# Sheet2.net
KiCad netlist of a schematic drawn in Altium Designer
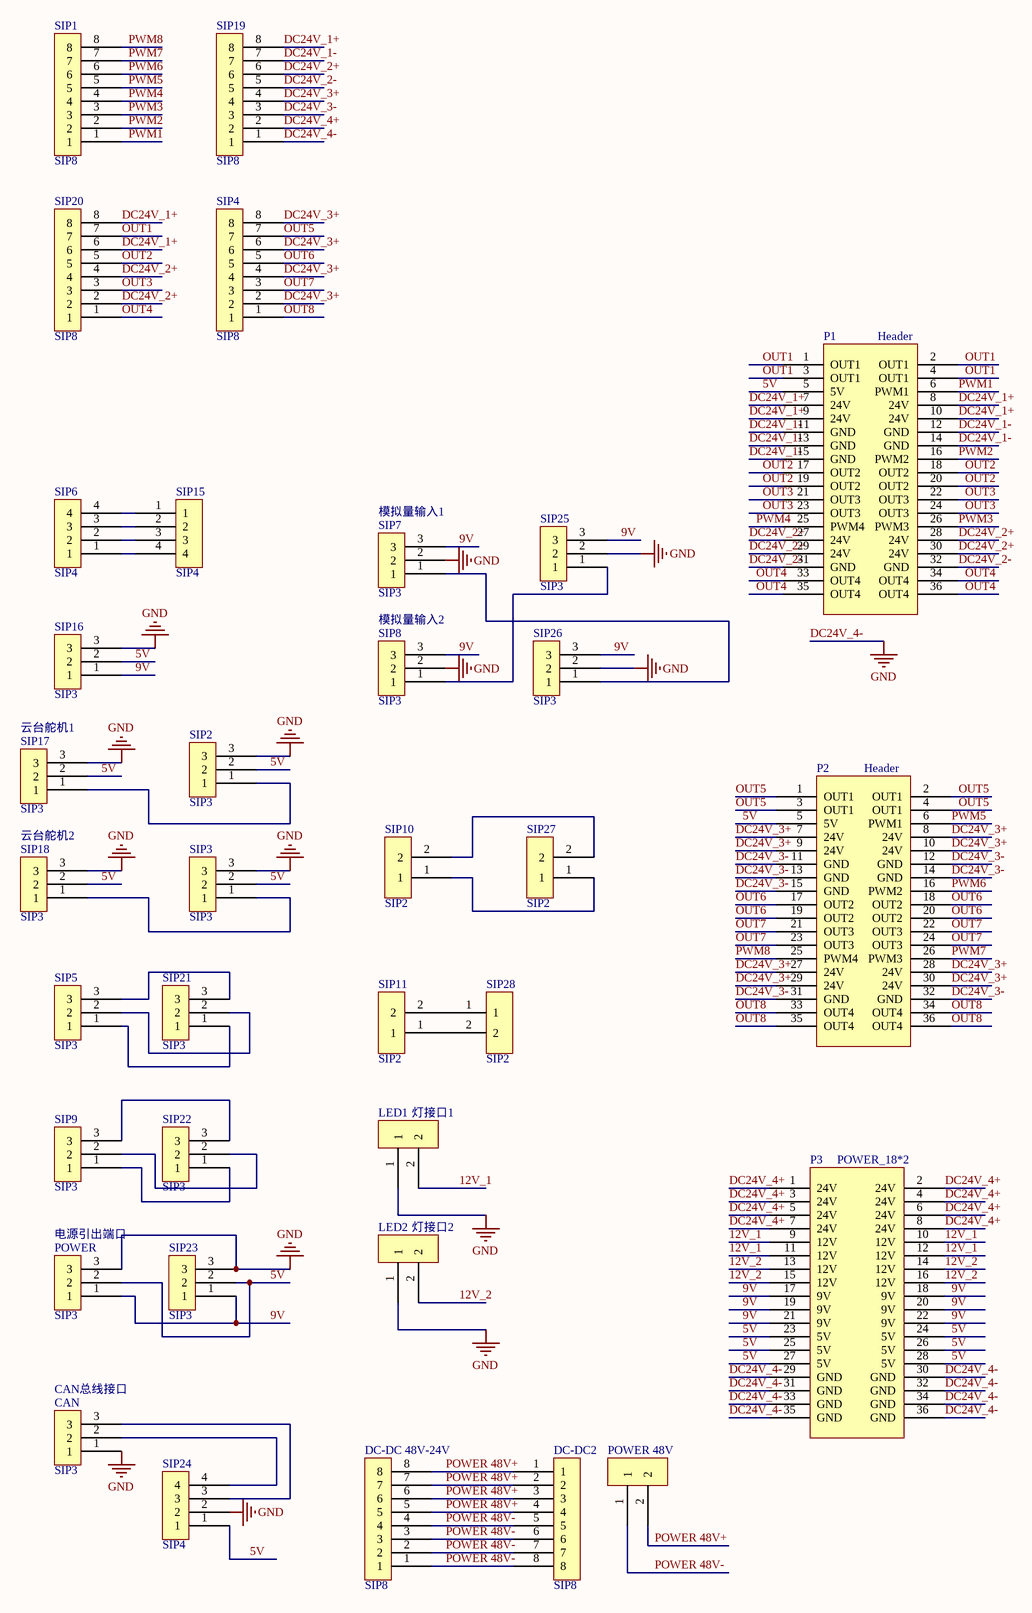
[diagram p0: Sheet2.SchDoc]

(export (version "E")
  (design (tool "Eeschema 10.0.6"))
  (components
    (comp (ref "CAN") (value "SIP3") (footprint "SIP3") (libsource (lib "qudong") (part "SIP3")))
    (comp (ref "DC-DC 48V-24V")
      (value "SIP8")
      (footprint "DIP8-3MM")
      (libsource (lib "qudong") (part "SIP8"))
    )
    (comp (ref "DC-DC2") (value "SIP8") (footprint "DIP8-3MM") (libsource (lib "") (part "SIP8_1")))
    (comp (ref "LED1") (value "SIP2") (footprint "SIP2-3MM") (libsource (lib "") (part "SIP2_2")))
    (comp (ref "LED2") (value "SIP2") (footprint "SIP2-3MM") (libsource (lib "") (part "SIP2_2")))
    (comp (ref "P1") (value "Header") (footprint "DIP36-3.96MM") (libsource (lib "qudong") (part "Header")))
    (comp (ref "P2") (value "Header") (footprint "DIP36-3.96MM") (libsource (lib "qudong") (part "Header")))
    (comp (ref "P3")
      (value "POWER_18*2")
      (footprint "DIP36-3.96MM")
      (libsource (lib "qudong") (part "POWER_18*2"))
    )
    (comp (ref "POWER") (value "SIP3") (footprint "SIP3") (libsource (lib "qudong") (part "SIP3")))
    (comp (ref "POWER 48V") (value "SIP2") (footprint "SIP2-3MM") (libsource (lib "") (part "SIP2_2")))
    (comp (ref "SIP1") (value "SIP8") (footprint "SIP8") (libsource (lib "qudong") (part "SIP8")))
    (comp (ref "SIP2") (value "SIP3") (footprint "SIP3") (libsource (lib "qudong") (part "SIP3")))
    (comp (ref "SIP3") (value "SIP3") (footprint "SIP3") (libsource (lib "qudong") (part "SIP3")))
    (comp (ref "SIP4") (value "SIP8") (footprint "DIP8-3MM") (libsource (lib "qudong") (part "SIP8")))
    (comp (ref "SIP5") (value "SIP3") (footprint "SIP3") (libsource (lib "qudong") (part "SIP3")))
    (comp (ref "SIP6") (value "SIP4") (footprint "SIP4") (libsource (lib "qudong") (part "SIP4")))
    (comp (ref "SIP7") (value "SIP3") (footprint "SIP3") (libsource (lib "qudong") (part "SIP3")))
    (comp (ref "SIP8") (value "SIP3") (footprint "SIP3") (libsource (lib "qudong") (part "SIP3")))
    (comp (ref "SIP9") (value "SIP3") (footprint "SIP3") (libsource (lib "qudong") (part "SIP3")))
    (comp (ref "SIP10") (value "SIP2") (footprint "SIP2") (libsource (lib "qudong") (part "SIP2")))
    (comp (ref "SIP11") (value "SIP2") (footprint "SIP2") (libsource (lib "qudong") (part "SIP2")))
    (comp (ref "SIP15") (value "SIP4") (footprint "SIP4") (libsource (lib "") (part "SIP4_1")))
    (comp (ref "SIP16") (value "SIP3") (footprint "SIP3") (libsource (lib "qudong") (part "SIP3")))
    (comp (ref "SIP17") (value "SIP3") (footprint "SIP3") (libsource (lib "qudong") (part "SIP3")))
    (comp (ref "SIP18") (value "SIP3") (footprint "SIP3") (libsource (lib "qudong") (part "SIP3")))
    (comp (ref "SIP19") (value "SIP8") (footprint "DIP8-3MM") (libsource (lib "qudong") (part "SIP8")))
    (comp (ref "SIP20") (value "SIP8") (footprint "DIP8-3MM") (libsource (lib "qudong") (part "SIP8")))
    (comp (ref "SIP21") (value "SIP3") (footprint "SIP3") (libsource (lib "qudong") (part "SIP3")))
    (comp (ref "SIP22") (value "SIP3") (footprint "SIP3") (libsource (lib "qudong") (part "SIP3")))
    (comp (ref "SIP23") (value "SIP3") (footprint "SIP3") (libsource (lib "qudong") (part "SIP3")))
    (comp (ref "SIP24") (value "SIP4") (footprint "SIP4") (libsource (lib "qudong") (part "SIP4")))
    (comp (ref "SIP25") (value "SIP3") (footprint "SIP3") (libsource (lib "qudong") (part "SIP3")))
    (comp (ref "SIP26") (value "SIP3") (footprint "SIP3") (libsource (lib "qudong") (part "SIP3")))
    (comp (ref "SIP27") (value "SIP2") (footprint "SIP2") (libsource (lib "qudong") (part "SIP2")))
    (comp (ref "SIP28") (value "SIP2") (footprint "SIP2") (libsource (lib "") (part "SIP2_1")))
  )
  (nets
    (net (code "1") (name "/5V") (class "Default")
      (node (ref "P1") (pin "5") (pinfunction "5V_5") (pintype "passive"))
      (node (ref "P2") (pin "5") (pinfunction "5V_5") (pintype "passive"))
      (node (ref "P3") (pin "23") (pinfunction "5V_23") (pintype "passive"))
      (node (ref "P3") (pin "24") (pinfunction "5V_24") (pintype "passive"))
      (node (ref "P3") (pin "25") (pinfunction "5V_25") (pintype "passive"))
      (node (ref "P3") (pin "26") (pinfunction "5V_26") (pintype "passive"))
      (node (ref "P3") (pin "27") (pinfunction "5V_27") (pintype "passive"))
      (node (ref "P3") (pin "28") (pinfunction "5V_28") (pintype "passive"))
      (node (ref "POWER") (pin "2") (pinfunction "2_2") (pintype "passive"))
      (node (ref "SIP16") (pin "2") (pinfunction "2_2") (pintype "passive"))
      (node (ref "SIP17") (pin "2") (pinfunction "2_2") (pintype "passive"))
      (node (ref "SIP18") (pin "2") (pinfunction "2_2") (pintype "passive"))
      (node (ref "SIP2") (pin "2") (pinfunction "2_2") (pintype "passive"))
      (node (ref "SIP23") (pin "2") (pinfunction "2_2") (pintype "passive"))
      (node (ref "SIP24") (pin "1") (pinfunction "1_1") (pintype "passive"))
      (node (ref "SIP3") (pin "2") (pinfunction "2_2") (pintype "passive"))
    )
    (net (code "2") (name "/9V") (class "Default")
      (node (ref "P3") (pin "17") (pinfunction "9V_17") (pintype "passive"))
      (node (ref "P3") (pin "18") (pinfunction "9V_18") (pintype "passive"))
      (node (ref "P3") (pin "19") (pinfunction "9V_19") (pintype "passive"))
      (node (ref "P3") (pin "20") (pinfunction "9V_20") (pintype "passive"))
      (node (ref "P3") (pin "21") (pinfunction "9V_21") (pintype "passive"))
      (node (ref "P3") (pin "22") (pinfunction "9V_22") (pintype "passive"))
      (node (ref "POWER") (pin "1") (pinfunction "1_1") (pintype "passive"))
      (node (ref "SIP16") (pin "1") (pinfunction "1_1") (pintype "passive"))
      (node (ref "SIP23") (pin "1") (pinfunction "1_1") (pintype "passive"))
      (node (ref "SIP25") (pin "3") (pinfunction "3_3") (pintype "passive"))
      (node (ref "SIP26") (pin "3") (pinfunction "3_3") (pintype "passive"))
      (node (ref "SIP7") (pin "3") (pinfunction "3_3") (pintype "passive"))
      (node (ref "SIP8") (pin "3") (pinfunction "3_3") (pintype "passive"))
    )
    (net (code "3") (name "/12V_1") (class "Default")
      (node (ref "LED1") (pin "2") (pinfunction "2_2") (pintype "passive"))
      (node (ref "P3") (pin "10") (pinfunction "12V_10") (pintype "passive"))
      (node (ref "P3") (pin "11") (pinfunction "12V_11") (pintype "passive"))
      (node (ref "P3") (pin "12") (pinfunction "12V_12") (pintype "passive"))
      (node (ref "P3") (pin "9") (pinfunction "12V_9") (pintype "passive"))
    )
    (net (code "4") (name "/12V_2") (class "Default")
      (node (ref "LED2") (pin "2") (pinfunction "2_2") (pintype "passive"))
      (node (ref "P3") (pin "13") (pinfunction "12V_13") (pintype "passive"))
      (node (ref "P3") (pin "14") (pinfunction "12V_14") (pintype "passive"))
      (node (ref "P3") (pin "15") (pinfunction "12V_15") (pintype "passive"))
      (node (ref "P3") (pin "16") (pinfunction "12V_16") (pintype "passive"))
    )
    (net (code "5") (name "/DC24V_1+") (class "Default")
      (node (ref "P1") (pin "10") (pinfunction "24V_10") (pintype "passive"))
      (node (ref "P1") (pin "7") (pinfunction "24V_7") (pintype "passive"))
      (node (ref "P1") (pin "8") (pinfunction "24V_8") (pintype "passive"))
      (node (ref "P1") (pin "9") (pinfunction "24V_9") (pintype "passive"))
      (node (ref "SIP19") (pin "8") (pinfunction "8_8") (pintype "passive"))
      (node (ref "SIP20") (pin "6") (pinfunction "6_6") (pintype "passive"))
      (node (ref "SIP20") (pin "8") (pinfunction "8_8") (pintype "passive"))
    )
    (net (code "6") (name "/DC24V_1-") (class "Default")
      (node (ref "P1") (pin "11") (pinfunction "GND_11") (pintype "passive"))
      (node (ref "P1") (pin "12") (pinfunction "GND_12") (pintype "passive"))
      (node (ref "P1") (pin "13") (pinfunction "GND_13") (pintype "passive"))
      (node (ref "P1") (pin "14") (pinfunction "GND_14") (pintype "passive"))
      (node (ref "P1") (pin "15") (pinfunction "GND_15") (pintype "passive"))
      (node (ref "SIP19") (pin "7") (pinfunction "7_7") (pintype "passive"))
    )
    (net (code "7") (name "/DC24V_2+") (class "Default")
      (node (ref "P1") (pin "27") (pinfunction "24V_27") (pintype "passive"))
      (node (ref "P1") (pin "28") (pinfunction "24V_28") (pintype "passive"))
      (node (ref "P1") (pin "29") (pinfunction "24V_29") (pintype "passive"))
      (node (ref "P1") (pin "30") (pinfunction "24V_30") (pintype "passive"))
      (node (ref "SIP19") (pin "6") (pinfunction "6_6") (pintype "passive"))
      (node (ref "SIP20") (pin "2") (pinfunction "2_2") (pintype "passive"))
      (node (ref "SIP20") (pin "4") (pinfunction "4_4") (pintype "passive"))
    )
    (net (code "8") (name "/DC24V_2-") (class "Default")
      (node (ref "P1") (pin "31") (pinfunction "GND_31") (pintype "passive"))
      (node (ref "P1") (pin "32") (pinfunction "GND_32") (pintype "passive"))
      (node (ref "SIP19") (pin "5") (pinfunction "5_5") (pintype "passive"))
    )
    (net (code "9") (name "/DC24V_3+") (class "Default")
      (node (ref "P2") (pin "10") (pinfunction "24V_10") (pintype "passive"))
      (node (ref "P2") (pin "27") (pinfunction "24V_27") (pintype "passive"))
      (node (ref "P2") (pin "28") (pinfunction "24V_28") (pintype "passive"))
      (node (ref "P2") (pin "29") (pinfunction "24V_29") (pintype "passive"))
      (node (ref "P2") (pin "30") (pinfunction "24V_30") (pintype "passive"))
      (node (ref "P2") (pin "7") (pinfunction "24V_7") (pintype "passive"))
      (node (ref "P2") (pin "8") (pinfunction "24V_8") (pintype "passive"))
      (node (ref "P2") (pin "9") (pinfunction "24V_9") (pintype "passive"))
      (node (ref "SIP19") (pin "4") (pinfunction "4_4") (pintype "passive"))
      (node (ref "SIP4") (pin "2") (pinfunction "2_2") (pintype "passive"))
      (node (ref "SIP4") (pin "4") (pinfunction "4_4") (pintype "passive"))
      (node (ref "SIP4") (pin "6") (pinfunction "6_6") (pintype "passive"))
      (node (ref "SIP4") (pin "8") (pinfunction "8_8") (pintype "passive"))
    )
    (net (code "10") (name "/DC24V_3-") (class "Default")
      (node (ref "P2") (pin "11") (pinfunction "GND_11") (pintype "passive"))
      (node (ref "P2") (pin "12") (pinfunction "GND_12") (pintype "passive"))
      (node (ref "P2") (pin "13") (pinfunction "GND_13") (pintype "passive"))
      (node (ref "P2") (pin "14") (pinfunction "GND_14") (pintype "passive"))
      (node (ref "P2") (pin "15") (pinfunction "GND_15") (pintype "passive"))
      (node (ref "P2") (pin "31") (pinfunction "GND_31") (pintype "passive"))
      (node (ref "P2") (pin "32") (pinfunction "GND_32") (pintype "passive"))
      (node (ref "SIP19") (pin "3") (pinfunction "3_3") (pintype "passive"))
    )
    (net (code "11") (name "/DC24V_4+") (class "Default")
      (node (ref "P3") (pin "1") (pinfunction "24V_1") (pintype "passive"))
      (node (ref "P3") (pin "2") (pinfunction "24V_2") (pintype "passive"))
      (node (ref "P3") (pin "3") (pinfunction "24V_3") (pintype "passive"))
      (node (ref "P3") (pin "4") (pinfunction "24V_4") (pintype "passive"))
      (node (ref "P3") (pin "5") (pinfunction "24V_5") (pintype "passive"))
      (node (ref "P3") (pin "6") (pinfunction "24V_6") (pintype "passive"))
      (node (ref "P3") (pin "7") (pinfunction "24V_7") (pintype "passive"))
      (node (ref "P3") (pin "8") (pinfunction "24V_8") (pintype "passive"))
      (node (ref "SIP19") (pin "2") (pinfunction "2_2") (pintype "passive"))
    )
    (net (code "12") (name "/OUT1") (class "Default")
      (node (ref "P1") (pin "1") (pinfunction "OUT1_1") (pintype "passive"))
      (node (ref "P1") (pin "2") (pinfunction "OUT1_2") (pintype "passive"))
      (node (ref "P1") (pin "3") (pinfunction "OUT1_3") (pintype "passive"))
      (node (ref "P1") (pin "4") (pinfunction "OUT1_4") (pintype "passive"))
      (node (ref "SIP20") (pin "7") (pinfunction "7_7") (pintype "passive"))
    )
    (net (code "13") (name "/OUT2") (class "Default")
      (node (ref "P1") (pin "17") (pinfunction "OUT2_17") (pintype "passive"))
      (node (ref "P1") (pin "18") (pinfunction "OUT2_18") (pintype "passive"))
      (node (ref "P1") (pin "19") (pinfunction "OUT2_19") (pintype "passive"))
      (node (ref "P1") (pin "20") (pinfunction "OUT2_20") (pintype "passive"))
      (node (ref "SIP20") (pin "5") (pinfunction "5_5") (pintype "passive"))
    )
    (net (code "14") (name "/OUT3") (class "Default")
      (node (ref "P1") (pin "21") (pinfunction "OUT3_21") (pintype "passive"))
      (node (ref "P1") (pin "22") (pinfunction "OUT3_22") (pintype "passive"))
      (node (ref "P1") (pin "23") (pinfunction "OUT3_23") (pintype "passive"))
      (node (ref "P1") (pin "24") (pinfunction "OUT3_24") (pintype "passive"))
      (node (ref "SIP20") (pin "3") (pinfunction "3_3") (pintype "passive"))
    )
    (net (code "15") (name "/OUT4") (class "Default")
      (node (ref "P1") (pin "33") (pinfunction "OUT4_33") (pintype "passive"))
      (node (ref "P1") (pin "34") (pinfunction "OUT4_34") (pintype "passive"))
      (node (ref "P1") (pin "35") (pinfunction "OUT4_35") (pintype "passive"))
      (node (ref "P1") (pin "36") (pinfunction "OUT4_36") (pintype "passive"))
      (node (ref "SIP20") (pin "1") (pinfunction "1_1") (pintype "passive"))
    )
    (net (code "16") (name "/OUT5") (class "Default")
      (node (ref "P2") (pin "1") (pinfunction "OUT1_1") (pintype "passive"))
      (node (ref "P2") (pin "2") (pinfunction "OUT1_2") (pintype "passive"))
      (node (ref "P2") (pin "3") (pinfunction "OUT1_3") (pintype "passive"))
      (node (ref "P2") (pin "4") (pinfunction "OUT1_4") (pintype "passive"))
      (node (ref "SIP4") (pin "7") (pinfunction "7_7") (pintype "passive"))
    )
    (net (code "17") (name "/OUT6") (class "Default")
      (node (ref "P2") (pin "17") (pinfunction "OUT2_17") (pintype "passive"))
      (node (ref "P2") (pin "18") (pinfunction "OUT2_18") (pintype "passive"))
      (node (ref "P2") (pin "19") (pinfunction "OUT2_19") (pintype "passive"))
      (node (ref "P2") (pin "20") (pinfunction "OUT2_20") (pintype "passive"))
      (node (ref "SIP4") (pin "5") (pinfunction "5_5") (pintype "passive"))
    )
    (net (code "18") (name "/OUT7") (class "Default")
      (node (ref "P2") (pin "21") (pinfunction "OUT3_21") (pintype "passive"))
      (node (ref "P2") (pin "22") (pinfunction "OUT3_22") (pintype "passive"))
      (node (ref "P2") (pin "23") (pinfunction "OUT3_23") (pintype "passive"))
      (node (ref "P2") (pin "24") (pinfunction "OUT3_24") (pintype "passive"))
      (node (ref "SIP4") (pin "3") (pinfunction "3_3") (pintype "passive"))
    )
    (net (code "19") (name "/OUT8") (class "Default")
      (node (ref "P2") (pin "33") (pinfunction "OUT4_33") (pintype "passive"))
      (node (ref "P2") (pin "34") (pinfunction "OUT4_34") (pintype "passive"))
      (node (ref "P2") (pin "35") (pinfunction "OUT4_35") (pintype "passive"))
      (node (ref "P2") (pin "36") (pinfunction "OUT4_36") (pintype "passive"))
      (node (ref "SIP4") (pin "1") (pinfunction "1_1") (pintype "passive"))
    )
    (net (code "20") (name "/POWER 48V+") (class "Default")
      (node (ref "DC-DC 48V-24V") (pin "5") (pinfunction "5_5") (pintype "passive"))
      (node (ref "DC-DC 48V-24V") (pin "6") (pinfunction "6_6") (pintype "passive"))
      (node (ref "DC-DC 48V-24V") (pin "7") (pinfunction "7_7") (pintype "passive"))
      (node (ref "DC-DC 48V-24V") (pin "8") (pinfunction "8_8") (pintype "passive"))
      (node (ref "DC-DC2") (pin "1") (pinfunction "1_1") (pintype "passive"))
      (node (ref "DC-DC2") (pin "2") (pinfunction "2_2") (pintype "passive"))
      (node (ref "DC-DC2") (pin "3") (pinfunction "3_3") (pintype "passive"))
      (node (ref "DC-DC2") (pin "4") (pinfunction "4_4") (pintype "passive"))
      (node (ref "POWER 48V") (pin "2") (pinfunction "2_2") (pintype "passive"))
    )
    (net (code "21") (name "/POWER 48V-") (class "Default")
      (node (ref "DC-DC 48V-24V") (pin "1") (pinfunction "1_1") (pintype "passive"))
      (node (ref "DC-DC 48V-24V") (pin "2") (pinfunction "2_2") (pintype "passive"))
      (node (ref "DC-DC 48V-24V") (pin "3") (pinfunction "3_3") (pintype "passive"))
      (node (ref "DC-DC 48V-24V") (pin "4") (pinfunction "4_4") (pintype "passive"))
      (node (ref "DC-DC2") (pin "5") (pinfunction "5_5") (pintype "passive"))
      (node (ref "DC-DC2") (pin "6") (pinfunction "6_6") (pintype "passive"))
      (node (ref "DC-DC2") (pin "7") (pinfunction "7_7") (pintype "passive"))
      (node (ref "DC-DC2") (pin "8") (pinfunction "8_8") (pintype "passive"))
      (node (ref "POWER 48V") (pin "1") (pinfunction "1_1") (pintype "passive"))
    )
    (net (code "22") (name "/PWM1") (class "Default")
      (node (ref "P1") (pin "6") (pinfunction "PWM1_6") (pintype "passive"))
      (node (ref "SIP1") (pin "1") (pinfunction "1_1") (pintype "passive"))
    )
    (net (code "23") (name "/PWM2") (class "Default")
      (node (ref "P1") (pin "16") (pinfunction "PWM2_16") (pintype "passive"))
      (node (ref "SIP1") (pin "2") (pinfunction "2_2") (pintype "passive"))
    )
    (net (code "24") (name "/PWM3") (class "Default")
      (node (ref "P1") (pin "26") (pinfunction "PWM3_26") (pintype "passive"))
      (node (ref "SIP1") (pin "3") (pinfunction "3_3") (pintype "passive"))
    )
    (net (code "25") (name "/PWM4") (class "Default")
      (node (ref "P1") (pin "25") (pinfunction "PWM4_25") (pintype "passive"))
      (node (ref "SIP1") (pin "4") (pinfunction "4_4") (pintype "passive"))
    )
    (net (code "26") (name "/PWM5") (class "Default")
      (node (ref "P2") (pin "6") (pinfunction "PWM1_6") (pintype "passive"))
      (node (ref "SIP1") (pin "5") (pinfunction "5_5") (pintype "passive"))
    )
    (net (code "27") (name "/PWM6") (class "Default")
      (node (ref "P2") (pin "16") (pinfunction "PWM2_16") (pintype "passive"))
      (node (ref "SIP1") (pin "6") (pinfunction "6_6") (pintype "passive"))
    )
    (net (code "28") (name "/PWM7") (class "Default")
      (node (ref "P2") (pin "26") (pinfunction "PWM3_26") (pintype "passive"))
      (node (ref "SIP1") (pin "7") (pinfunction "7_7") (pintype "passive"))
    )
    (net (code "29") (name "/PWM8") (class "Default")
      (node (ref "P2") (pin "25") (pinfunction "PWM4_25") (pintype "passive"))
      (node (ref "SIP1") (pin "8") (pinfunction "8_8") (pintype "passive"))
    )
    (net (code "30") (name "GND") (class "Default")
      (node (ref "CAN") (pin "1") (pinfunction "1_1") (pintype "passive"))
      (node (ref "LED1") (pin "1") (pinfunction "1_1") (pintype "passive"))
      (node (ref "LED2") (pin "1") (pinfunction "1_1") (pintype "passive"))
      (node (ref "P3") (pin "29") (pinfunction "GND_29") (pintype "passive"))
      (node (ref "P3") (pin "30") (pinfunction "GND_30") (pintype "passive"))
      (node (ref "P3") (pin "31") (pinfunction "GND_31") (pintype "passive"))
      (node (ref "P3") (pin "32") (pinfunction "GND_32") (pintype "passive"))
      (node (ref "P3") (pin "33") (pinfunction "GND_33") (pintype "passive"))
      (node (ref "P3") (pin "34") (pinfunction "GND_34") (pintype "passive"))
      (node (ref "P3") (pin "35") (pinfunction "GND_35") (pintype "passive"))
      (node (ref "P3") (pin "36") (pinfunction "GND_36") (pintype "passive"))
      (node (ref "POWER") (pin "3") (pinfunction "3_3") (pintype "passive"))
      (node (ref "SIP16") (pin "3") (pinfunction "3_3") (pintype "passive"))
      (node (ref "SIP17") (pin "3") (pinfunction "3_3") (pintype "passive"))
      (node (ref "SIP18") (pin "3") (pinfunction "3_3") (pintype "passive"))
      (node (ref "SIP19") (pin "1") (pinfunction "1_1") (pintype "passive"))
      (node (ref "SIP2") (pin "3") (pinfunction "3_3") (pintype "passive"))
      (node (ref "SIP23") (pin "3") (pinfunction "3_3") (pintype "passive"))
      (node (ref "SIP24") (pin "2") (pinfunction "2_2") (pintype "passive"))
      (node (ref "SIP25") (pin "2") (pinfunction "2_2") (pintype "passive"))
      (node (ref "SIP26") (pin "2") (pinfunction "2_2") (pintype "passive"))
      (node (ref "SIP3") (pin "3") (pinfunction "3_3") (pintype "passive"))
      (node (ref "SIP7") (pin "2") (pinfunction "2_2") (pintype "passive"))
      (node (ref "SIP8") (pin "2") (pinfunction "2_2") (pintype "passive"))
    )
    (net (code "31") (name "Net-(CAN-Pad2)") (class "Default")
      (node (ref "CAN") (pin "2") (pinfunction "2_2") (pintype "passive"))
      (node (ref "SIP24") (pin "4") (pinfunction "4_4") (pintype "passive"))
    )
    (net (code "32") (name "Net-(CAN-Pad3)") (class "Default")
      (node (ref "CAN") (pin "3") (pinfunction "3_3") (pintype "passive"))
      (node (ref "SIP24") (pin "3") (pinfunction "3_3") (pintype "passive"))
    )
    (net (code "33") (name "Net-(SIP10-Pad1)") (class "Default")
      (node (ref "SIP10") (pin "1") (pinfunction "1_1") (pintype "passive"))
      (node (ref "SIP27") (pin "1") (pinfunction "1_1") (pintype "passive"))
    )
    (net (code "34") (name "Net-(SIP10-Pad2)") (class "Default")
      (node (ref "SIP10") (pin "2") (pinfunction "2_2") (pintype "passive"))
      (node (ref "SIP27") (pin "2") (pinfunction "2_2") (pintype "passive"))
    )
    (net (code "35") (name "Net-(SIP11-Pad1)") (class "Default")
      (node (ref "SIP11") (pin "1") (pinfunction "1_1") (pintype "passive"))
      (node (ref "SIP28") (pin "2") (pinfunction "2_2") (pintype "passive"))
    )
    (net (code "36") (name "Net-(SIP11-Pad2)") (class "Default")
      (node (ref "SIP11") (pin "2") (pinfunction "2_2") (pintype "passive"))
      (node (ref "SIP28") (pin "1") (pinfunction "1_1") (pintype "passive"))
    )
    (net (code "37") (name "Net-(SIP15-Pad1)") (class "Default")
      (node (ref "SIP15") (pin "1") (pinfunction "1_1") (pintype "passive"))
      (node (ref "SIP6") (pin "4") (pinfunction "4_4") (pintype "passive"))
    )
    (net (code "38") (name "Net-(SIP15-Pad2)") (class "Default")
      (node (ref "SIP15") (pin "2") (pinfunction "2_2") (pintype "passive"))
      (node (ref "SIP6") (pin "3") (pinfunction "3_3") (pintype "passive"))
    )
    (net (code "39") (name "Net-(SIP15-Pad3)") (class "Default")
      (node (ref "SIP15") (pin "3") (pinfunction "3_3") (pintype "passive"))
      (node (ref "SIP6") (pin "2") (pinfunction "2_2") (pintype "passive"))
    )
    (net (code "40") (name "Net-(SIP15-Pad4)") (class "Default")
      (node (ref "SIP15") (pin "4") (pinfunction "4_4") (pintype "passive"))
      (node (ref "SIP6") (pin "1") (pinfunction "1_1") (pintype "passive"))
    )
    (net (code "41") (name "Net-(SIP17-Pad1)") (class "Default")
      (node (ref "SIP17") (pin "1") (pinfunction "1_1") (pintype "passive"))
      (node (ref "SIP2") (pin "1") (pinfunction "1_1") (pintype "passive"))
    )
    (net (code "42") (name "Net-(SIP18-Pad1)") (class "Default")
      (node (ref "SIP18") (pin "1") (pinfunction "1_1") (pintype "passive"))
      (node (ref "SIP3") (pin "1") (pinfunction "1_1") (pintype "passive"))
    )
    (net (code "43") (name "Net-(SIP21-Pad1)") (class "Default")
      (node (ref "SIP21") (pin "1") (pinfunction "1_1") (pintype "passive"))
      (node (ref "SIP5") (pin "1") (pinfunction "1_1") (pintype "passive"))
    )
    (net (code "44") (name "Net-(SIP21-Pad2)") (class "Default")
      (node (ref "SIP21") (pin "2") (pinfunction "2_2") (pintype "passive"))
      (node (ref "SIP5") (pin "2") (pinfunction "2_2") (pintype "passive"))
    )
    (net (code "45") (name "Net-(SIP21-Pad3)") (class "Default")
      (node (ref "SIP21") (pin "3") (pinfunction "3_3") (pintype "passive"))
      (node (ref "SIP5") (pin "3") (pinfunction "3_3") (pintype "passive"))
    )
    (net (code "46") (name "Net-(SIP22-Pad1)") (class "Default")
      (node (ref "SIP22") (pin "1") (pinfunction "1_1") (pintype "passive"))
      (node (ref "SIP9") (pin "1") (pinfunction "1_1") (pintype "passive"))
    )
    (net (code "47") (name "Net-(SIP22-Pad2)") (class "Default")
      (node (ref "SIP22") (pin "2") (pinfunction "2_2") (pintype "passive"))
      (node (ref "SIP9") (pin "2") (pinfunction "2_2") (pintype "passive"))
    )
    (net (code "48") (name "Net-(SIP22-Pad3)") (class "Default")
      (node (ref "SIP22") (pin "3") (pinfunction "3_3") (pintype "passive"))
      (node (ref "SIP9") (pin "3") (pinfunction "3_3") (pintype "passive"))
    )
    (net (code "49") (name "Net-(SIP25-Pad1)") (class "Default")
      (node (ref "SIP25") (pin "1") (pinfunction "1_1") (pintype "passive"))
      (node (ref "SIP8") (pin "1") (pinfunction "1_1") (pintype "passive"))
    )
    (net (code "50") (name "Net-(SIP26-Pad1)") (class "Default")
      (node (ref "SIP26") (pin "1") (pinfunction "1_1") (pintype "passive"))
      (node (ref "SIP7") (pin "1") (pinfunction "1_1") (pintype "passive"))
    )
  )
)
